# TESTED_Midi2PO.net
KiCad netlist of a schematic drawn in EAGLE
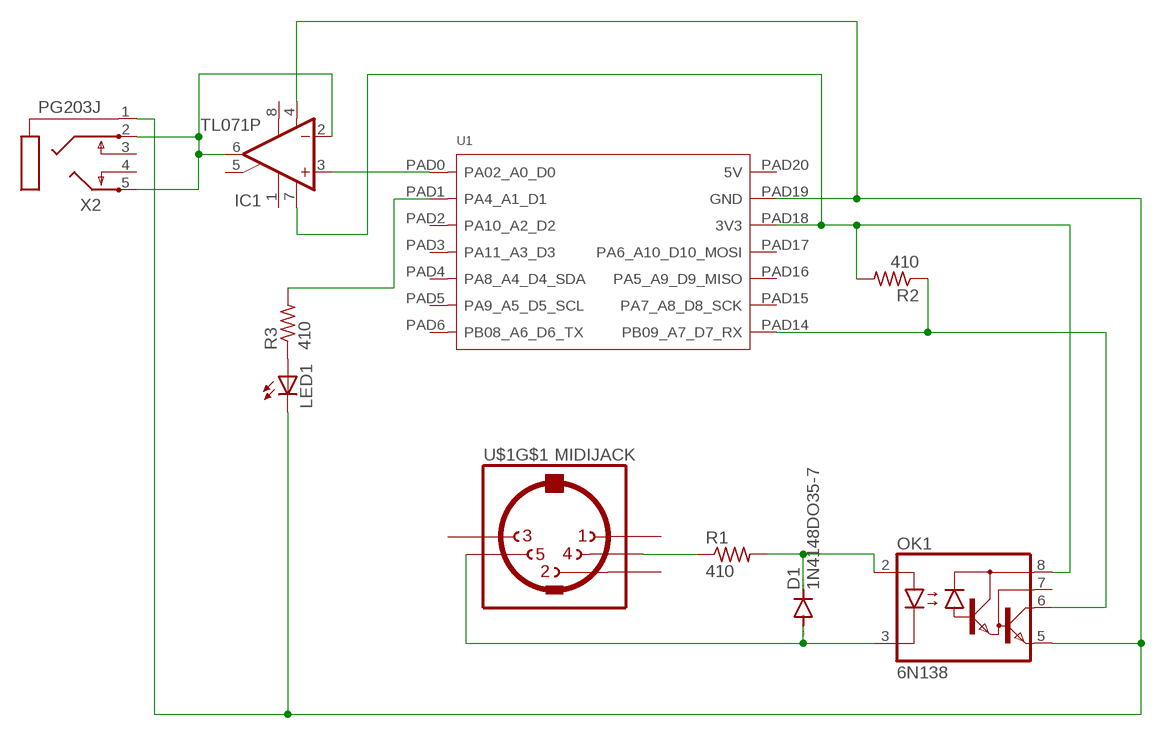
[diagram p0: schematic, sheet 1]

(export (version "E")
  (design (tool "Eeschema 10.0.6"))
  (components
    (comp (ref "D1")
      (value "1N4148DO35-7")
      (footprint "eagle-import:DO35-7")
      (libsource (lib "eagle-import") (part "1N4148DO35-7"))
    )
    (comp (ref "IC1")
      (value "TL071P")
      (footprint "eagle-import:DIL08")
      (libsource (lib "eagle-import") (part "TL071P"))
    )
    (comp (ref "LED1")
      (value "LED5MM")
      (footprint "eagle-import:LED5MM")
      (libsource (lib "eagle-import") (part "LED5MM"))
    )
    (comp (ref "OK1")
      (value "6N138")
      (footprint "eagle-import:DIL08")
      (fields (field (name "MF") "VISHAY/TELEFUNKEN"))
      (libsource (lib "eagle-import") (part "6N138"))
    )
    (comp (ref "R1")
      (value "410")
      (footprint "eagle-import:0207_9")
      (libsource (lib "eagle-import") (part "R-US_0207/9"))
    )
    (comp (ref "R2")
      (value "410")
      (footprint "eagle-import:0207_9")
      (libsource (lib "eagle-import") (part "R-US_0207/9"))
    )
    (comp (ref "R3")
      (value "410")
      (footprint "eagle-import:0207_9")
      (libsource (lib "eagle-import") (part "R-US_0207/9"))
    )
    (comp (ref "U$1")
      (value "MIDIJACK")
      (footprint "eagle-import:CP-2350")
      (libsource (lib "eagle-import") (part "MIDIJACK"))
    )
    (comp (ref "U1")
      (value "MOUDLE-SEEEDUINO-XIAO")
      (footprint "eagle-import:MOUDLE14P-2.54-21X17.8MM")
      (libsource (lib "eagle-import") (part "MOUDLE-SEEEDUINO-XIAO"))
    )
    (comp (ref "X2")
      (value "PG203J")
      (footprint "eagle-import:PG203J")
      (libsource (lib "eagle-import") (part "PG203J"))
    )
  )
  (nets
    (net (code "1") (name "Net-(IC1-+IN)") (class "Default")
      (node (ref "IC1") (pin "3") (pinfunction "+IN_3") (pintype "input"))
      (node (ref "U1") (pin "PAD0") (pinfunction "PA02_A0_D0_PAD0") (pintype "bidirectional"))
    )
    (net (code "2") (name "Net-(IC1--IN)") (class "Default")
      (node (ref "IC1") (pin "2") (pinfunction "-IN_2") (pintype "input"))
      (node (ref "IC1") (pin "6") (pinfunction "OUT_6") (pintype "output"))
      (node (ref "X2") (pin "2") (pinfunction "2_2") (pintype "passive"))
      (node (ref "X2") (pin "5") (pinfunction "5_5") (pintype "passive"))
    )
    (net (code "3") (name "Net-(IC1-V+)") (class "Default")
      (node (ref "IC1") (pin "7") (pinfunction "V+_7") (pintype "power_in"))
      (node (ref "OK1") (pin "8") (pinfunction "VCC_8") (pintype "passive"))
      (node (ref "R2") (pin "2") (pinfunction "2_2") (pintype "passive"))
      (node (ref "U1") (pin "PAD18") (pinfunction "3V3_PAD18") (pintype "bidirectional"))
    )
    (net (code "4") (name "Net-(IC1-V-)") (class "Default")
      (node (ref "IC1") (pin "4") (pinfunction "V-_4") (pintype "power_in"))
      (node (ref "LED1") (pin "K") (pinfunction "C_K") (pintype "passive"))
      (node (ref "OK1") (pin "5") (pinfunction "GND_5") (pintype "passive"))
      (node (ref "U1") (pin "PAD19") (pinfunction "GND_PAD19") (pintype "bidirectional"))
      (node (ref "X2") (pin "1") (pinfunction "1_1") (pintype "passive"))
    )
    (net (code "5") (name "Net-(LED1-PadA)") (class "Default")
      (node (ref "LED1") (pin "A") (pinfunction "A_A") (pintype "passive"))
      (node (ref "R3") (pin "1") (pinfunction "1_1") (pintype "passive"))
    )
    (net (code "6") (name "Net-(OK1-A)") (class "Default")
      (node (ref "D1") (pin "C") (pinfunction "C_C") (pintype "passive"))
      (node (ref "OK1") (pin "2") (pinfunction "A_2") (pintype "passive"))
      (node (ref "R1") (pin "2") (pinfunction "2_2") (pintype "passive"))
    )
    (net (code "7") (name "Net-(OK1-C)") (class "Default")
      (node (ref "D1") (pin "A") (pinfunction "A_A") (pintype "passive"))
      (node (ref "OK1") (pin "3") (pinfunction "C_3") (pintype "passive"))
      (node (ref "U$1") (pin "5") (pinfunction "5_5") (pintype "passive"))
    )
    (net (code "8") (name "Net-(OK1-VO)") (class "Default")
      (node (ref "OK1") (pin "6") (pinfunction "VO_6") (pintype "passive"))
      (node (ref "R2") (pin "1") (pinfunction "1_1") (pintype "passive"))
      (node (ref "U1") (pin "PAD14") (pinfunction "PB09_A7_D7_RX_PAD14") (pintype "bidirectional"))
    )
    (net (code "9") (name "Net-(R1-Pad1)") (class "Default")
      (node (ref "R1") (pin "1") (pinfunction "1_1") (pintype "passive"))
      (node (ref "U$1") (pin "4") (pinfunction "4_4") (pintype "passive"))
    )
    (net (code "10") (name "Net-(U1-PA4_A1_D1)") (class "Default")
      (node (ref "R3") (pin "2") (pinfunction "2_2") (pintype "passive"))
      (node (ref "U1") (pin "PAD1") (pinfunction "PA4_A1_D1_PAD1") (pintype "bidirectional"))
    )
    (net (code "11") (name "unconnected-(IC1-ON1-Pad1)") (class "Default")
      (node (ref "IC1") (pin "1") (pinfunction "ON1_1") (pintype "passive"))
    )
    (net (code "12") (name "unconnected-(IC1-ON2-Pad5)") (class "Default")
      (node (ref "IC1") (pin "5") (pinfunction "ON2_5") (pintype "passive"))
    )
    (net (code "13") (name "unconnected-(IC1-OPT-Pad8)") (class "Default")
      (node (ref "IC1") (pin "8") (pinfunction "OPT_8") (pintype "passive"))
    )
    (net (code "14") (name "unconnected-(OK1-VB-Pad7)") (class "Default")
      (node (ref "OK1") (pin "7") (pinfunction "VB_7") (pintype "passive"))
    )
    (net (code "15") (name "unconnected-(U$1-Pad1)") (class "Default")
      (node (ref "U$1") (pin "1") (pinfunction "1_1") (pintype "passive"))
    )
    (net (code "16") (name "unconnected-(U$1-Pad2)") (class "Default")
      (node (ref "U$1") (pin "2") (pinfunction "2_2") (pintype "passive"))
    )
    (net (code "17") (name "unconnected-(U$1-Pad3)") (class "Default")
      (node (ref "U$1") (pin "3") (pinfunction "3_3") (pintype "passive"))
    )
    (net (code "18") (name "unconnected-(U1-5V-PadPAD20)") (class "Default")
      (node (ref "U1") (pin "PAD20") (pinfunction "5V_PAD20") (pintype "bidirectional"))
    )
    (net (code "19") (name "unconnected-(U1-PA5_A9_D9_MISO-PadPAD16)") (class "Default")
      (node (ref "U1") (pin "PAD16") (pinfunction "PA5_A9_D9_MISO_PAD16") (pintype "bidirectional"))
    )
    (net (code "20") (name "unconnected-(U1-PA6_A10_D10_MOSI-PadPAD17)") (class "Default")
      (node (ref "U1") (pin "PAD17") (pinfunction "PA6_A10_D10_MOSI_PAD17") (pintype "bidirectional"))
    )
    (net (code "21") (name "unconnected-(U1-PA7_A8_D8_SCK-PadPAD15)") (class "Default")
      (node (ref "U1") (pin "PAD15") (pinfunction "PA7_A8_D8_SCK_PAD15") (pintype "bidirectional"))
    )
    (net (code "22") (name "unconnected-(U1-PA8_A4_D4_SDA-PadPAD4)") (class "Default")
      (node (ref "U1") (pin "PAD4") (pinfunction "PA8_A4_D4_SDA_PAD4") (pintype "bidirectional"))
    )
    (net (code "23") (name "unconnected-(U1-PA9_A5_D5_SCL-PadPAD5)") (class "Default")
      (node (ref "U1") (pin "PAD5") (pinfunction "PA9_A5_D5_SCL_PAD5") (pintype "bidirectional"))
    )
    (net (code "24") (name "unconnected-(U1-PA10_A2_D2-PadPAD2)") (class "Default")
      (node (ref "U1") (pin "PAD2") (pinfunction "PA10_A2_D2_PAD2") (pintype "bidirectional"))
    )
    (net (code "25") (name "unconnected-(U1-PA11_A3_D3-PadPAD3)") (class "Default")
      (node (ref "U1") (pin "PAD3") (pinfunction "PA11_A3_D3_PAD3") (pintype "bidirectional"))
    )
    (net (code "26") (name "unconnected-(U1-PB08_A6_D6_TX-PadPAD6)") (class "Default")
      (node (ref "U1") (pin "PAD6") (pinfunction "PB08_A6_D6_TX_PAD6") (pintype "bidirectional"))
    )
    (net (code "27") (name "unconnected-(X2-Pad3)") (class "Default")
      (node (ref "X2") (pin "3") (pinfunction "3_3") (pintype "passive"))
    )
    (net (code "28") (name "unconnected-(X2-Pad4)") (class "Default")
      (node (ref "X2") (pin "4") (pinfunction "4_4") (pintype "passive"))
    )
  )
)
